# featherwing_RGBLEDmatrixPanel.net
KiCad netlist of a schematic drawn in EAGLE
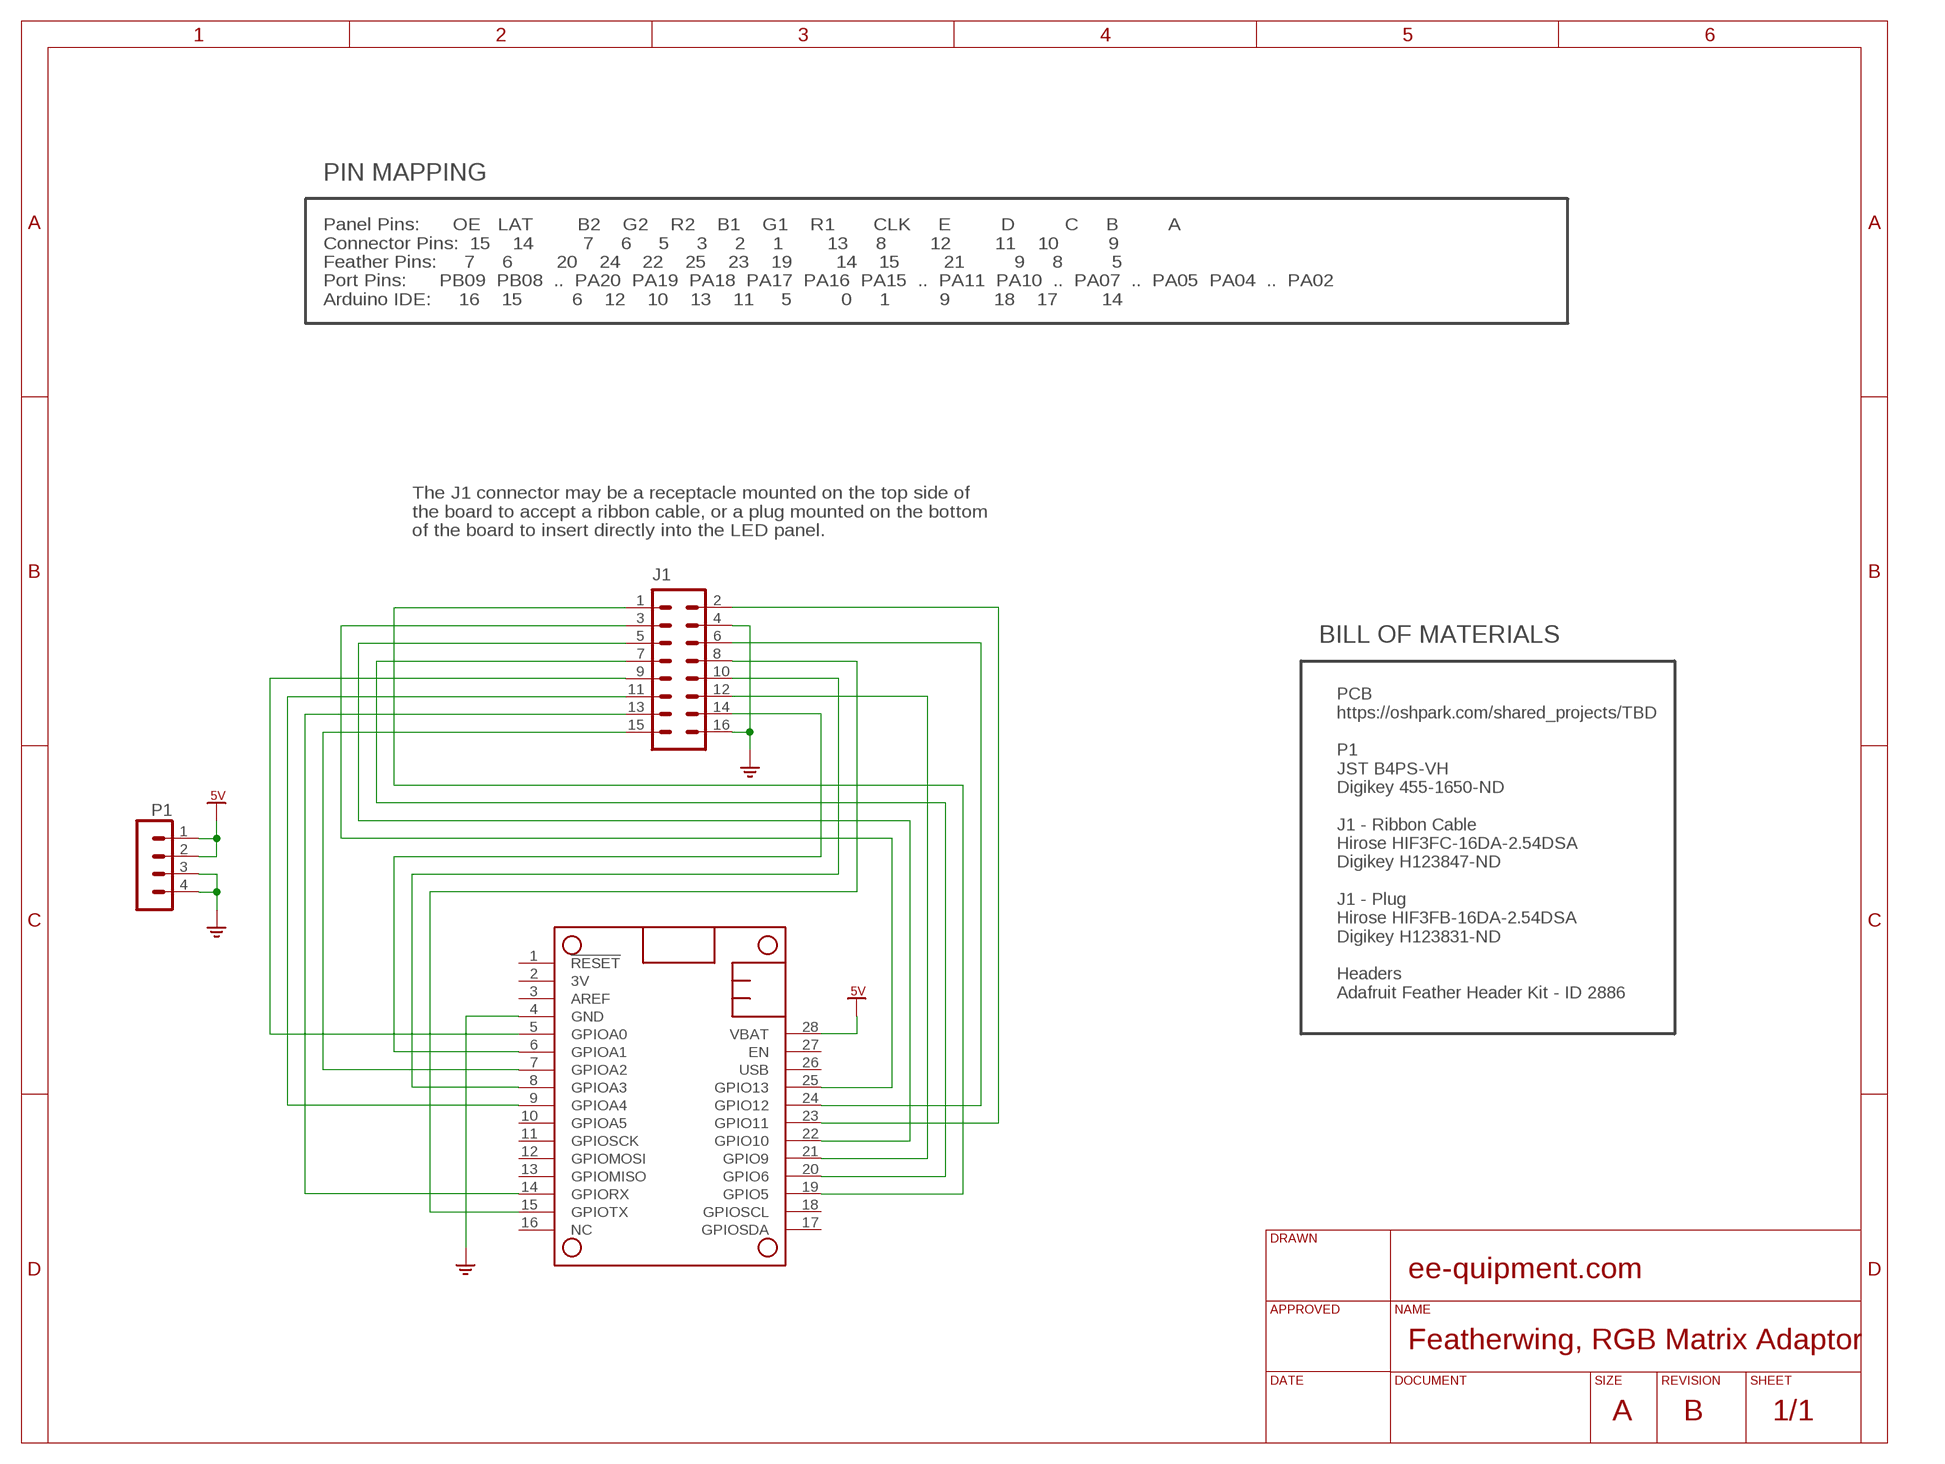
[diagram p0: schematic, sheet 1]

(export (version "E")
  (design (tool "Eeschema 10.0.6"))
  (components
    (comp (ref "J1")
      (value "HDR_16")
      (footprint "eagle-import:HDR_16")
      (libsource (lib "eagle-import") (part "HDR_16"))
    )
    (comp (ref "MS1")
      (value "MICROSHIELD")
      (footprint "eagle-import:MICROSHIELD")
      (libsource (lib "eagle-import") (part "MICROSHIELD"))
    )
    (comp (ref "P1")
      (value "JST_B4P-VHRA")
      (footprint "eagle-import:JST_B4PS-VH")
      (libsource (lib "eagle-import") (part "JST_B4P-VHRA"))
    )
  )
  (nets
    (net (code "1") (name "/3V") (class "Default")
      (node (ref "MS1") (pin "2") (pinfunction "3V_2") (pintype "power_in"))
    )
    (net (code "2") (name "/USB") (class "Default")
      (node (ref "MS1") (pin "26") (pinfunction "USB_26") (pintype "power_in"))
    )
    (net (code "3") (name "5V") (class "Default")
      (node (ref "MS1") (pin "28") (pinfunction "VBAT_28") (pintype "power_in"))
      (node (ref "P1") (pin "1") (pinfunction "1_1") (pintype "passive"))
      (node (ref "P1") (pin "2") (pinfunction "2_2") (pintype "passive"))
    )
    (net (code "4") (name "GND") (class "Default")
      (node (ref "J1") (pin "16") (pinfunction "16_16") (pintype "passive"))
      (node (ref "J1") (pin "4") (pinfunction "4_4") (pintype "passive"))
      (node (ref "MS1") (pin "4") (pinfunction "GND_4") (pintype "power_in"))
      (node (ref "P1") (pin "3") (pinfunction "3_3") (pintype "passive"))
      (node (ref "P1") (pin "4") (pinfunction "4_4") (pintype "passive"))
    )
    (net (code "5") (name "Net-(MS1-GPIO5)") (class "Default")
      (node (ref "J1") (pin "1") (pinfunction "1_1") (pintype "passive"))
      (node (ref "MS1") (pin "19") (pinfunction "GPIO5_19") (pintype "bidirectional"))
    )
    (net (code "6") (name "Net-(MS1-GPIO6)") (class "Default")
      (node (ref "J1") (pin "7") (pinfunction "7_7") (pintype "passive"))
      (node (ref "MS1") (pin "20") (pinfunction "GPIO6_20") (pintype "bidirectional"))
    )
    (net (code "7") (name "Net-(MS1-GPIO9)") (class "Default")
      (node (ref "J1") (pin "12") (pinfunction "12_12") (pintype "passive"))
      (node (ref "MS1") (pin "21") (pinfunction "GPIO9_21") (pintype "bidirectional"))
    )
    (net (code "8") (name "Net-(MS1-GPIO10)") (class "Default")
      (node (ref "J1") (pin "5") (pinfunction "5_5") (pintype "passive"))
      (node (ref "MS1") (pin "22") (pinfunction "GPIO10_22") (pintype "bidirectional"))
    )
    (net (code "9") (name "Net-(MS1-GPIO11)") (class "Default")
      (node (ref "J1") (pin "2") (pinfunction "2_2") (pintype "passive"))
      (node (ref "MS1") (pin "23") (pinfunction "GPIO11_23") (pintype "bidirectional"))
    )
    (net (code "10") (name "Net-(MS1-GPIO12)") (class "Default")
      (node (ref "J1") (pin "6") (pinfunction "6_6") (pintype "passive"))
      (node (ref "MS1") (pin "24") (pinfunction "GPIO12_24") (pintype "bidirectional"))
    )
    (net (code "11") (name "Net-(MS1-GPIO13)") (class "Default")
      (node (ref "J1") (pin "3") (pinfunction "3_3") (pintype "passive"))
      (node (ref "MS1") (pin "25") (pinfunction "GPIO13_25") (pintype "bidirectional"))
    )
    (net (code "12") (name "Net-(MS1-GPIOA0)") (class "Default")
      (node (ref "J1") (pin "9") (pinfunction "9_9") (pintype "passive"))
      (node (ref "MS1") (pin "5") (pinfunction "GPIOA0_5") (pintype "bidirectional"))
    )
    (net (code "13") (name "Net-(MS1-GPIOA1)") (class "Default")
      (node (ref "J1") (pin "14") (pinfunction "14_14") (pintype "passive"))
      (node (ref "MS1") (pin "6") (pinfunction "GPIOA1_6") (pintype "bidirectional"))
    )
    (net (code "14") (name "Net-(MS1-GPIOA2)") (class "Default")
      (node (ref "J1") (pin "15") (pinfunction "15_15") (pintype "passive"))
      (node (ref "MS1") (pin "7") (pinfunction "GPIOA2_7") (pintype "bidirectional"))
    )
    (net (code "15") (name "Net-(MS1-GPIOA3)") (class "Default")
      (node (ref "J1") (pin "10") (pinfunction "10_10") (pintype "passive"))
      (node (ref "MS1") (pin "8") (pinfunction "GPIOA3_8") (pintype "bidirectional"))
    )
    (net (code "16") (name "Net-(MS1-GPIOA4)") (class "Default")
      (node (ref "J1") (pin "11") (pinfunction "11_11") (pintype "passive"))
      (node (ref "MS1") (pin "9") (pinfunction "GPIOA4_9") (pintype "bidirectional"))
    )
    (net (code "17") (name "Net-(MS1-GPIORX)") (class "Default")
      (node (ref "J1") (pin "13") (pinfunction "13_13") (pintype "passive"))
      (node (ref "MS1") (pin "14") (pinfunction "GPIORX_14") (pintype "bidirectional"))
    )
    (net (code "18") (name "Net-(MS1-GPIOTX)") (class "Default")
      (node (ref "J1") (pin "8") (pinfunction "8_8") (pintype "passive"))
      (node (ref "MS1") (pin "15") (pinfunction "GPIOTX_15") (pintype "bidirectional"))
    )
    (net (code "19") (name "unconnected-(MS1-AREF-Pad3)") (class "Default")
      (node (ref "MS1") (pin "3") (pinfunction "AREF_3") (pintype "passive"))
    )
    (net (code "20") (name "unconnected-(MS1-EN-Pad27)") (class "Default")
      (node (ref "MS1") (pin "27") (pinfunction "EN_27") (pintype "passive"))
    )
    (net (code "21") (name "unconnected-(MS1-GPIOA5-Pad10)") (class "Default")
      (node (ref "MS1") (pin "10") (pinfunction "GPIOA5_10") (pintype "bidirectional"))
    )
    (net (code "22") (name "unconnected-(MS1-GPIOMISO-Pad13)") (class "Default")
      (node (ref "MS1") (pin "13") (pinfunction "GPIOMISO_13") (pintype "bidirectional"))
    )
    (net (code "23") (name "unconnected-(MS1-GPIOMOSI-Pad12)") (class "Default")
      (node (ref "MS1") (pin "12") (pinfunction "GPIOMOSI_12") (pintype "bidirectional"))
    )
    (net (code "24") (name "unconnected-(MS1-GPIOSCK-Pad11)") (class "Default")
      (node (ref "MS1") (pin "11") (pinfunction "GPIOSCK_11") (pintype "bidirectional"))
    )
    (net (code "25") (name "unconnected-(MS1-GPIOSCL-Pad18)") (class "Default")
      (node (ref "MS1") (pin "18") (pinfunction "GPIOSCL_18") (pintype "bidirectional"))
    )
    (net (code "26") (name "unconnected-(MS1-GPIOSDA-Pad17)") (class "Default")
      (node (ref "MS1") (pin "17") (pinfunction "GPIOSDA_17") (pintype "bidirectional"))
    )
    (net (code "27") (name "unconnected-(MS1-NC-Pad16)") (class "Default")
      (node (ref "MS1") (pin "16") (pinfunction "NC_16") (pintype "passive"))
    )
    (net (code "28") (name "unconnected-(MS1-~{RESET}-Pad1)") (class "Default")
      (node (ref "MS1") (pin "1") (pinfunction "~{RESET}_1") (pintype "input"))
    )
  )
)
